# Logica_ADC.net
KiCad netlist of a schematic drawn in Altium Designer
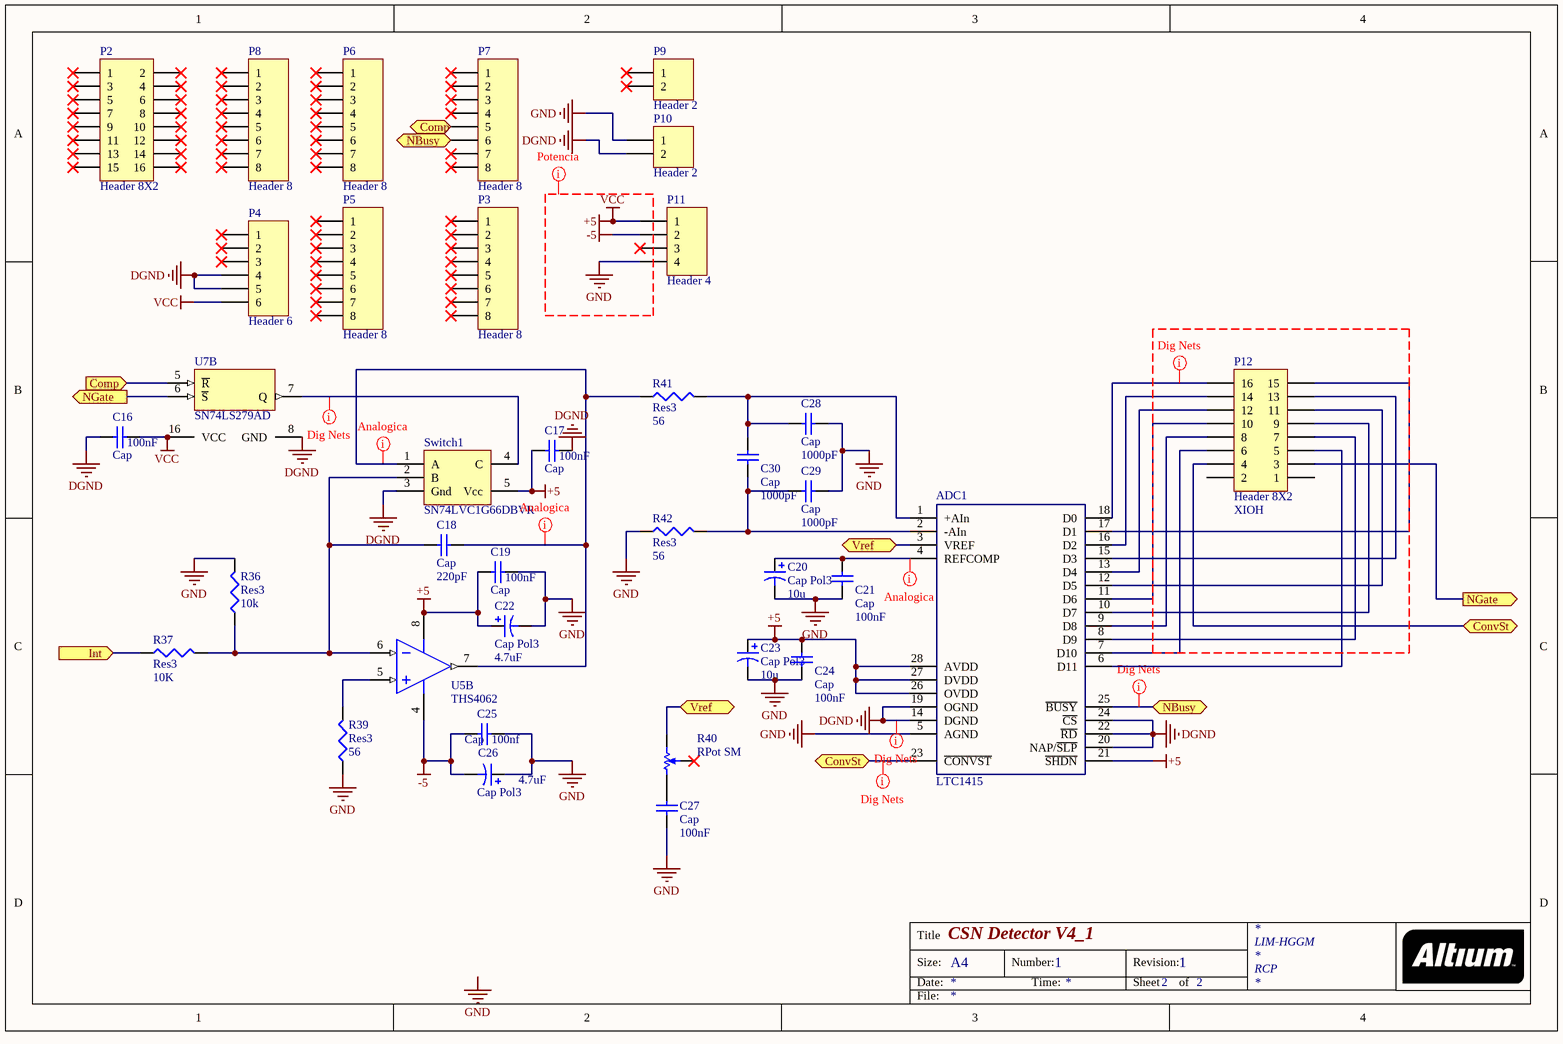
[diagram p0: Logica_ADC.SchDoc]

(export (version "E")
  (design (tool "Eeschema 10.0.6"))
  (components
    (comp (ref "ADC1")
      (value "LTC1415")
      (footprint "SO28_N")
      (libsource (lib "Integrated_Library1") (part "LTC1415"))
    )
    (comp (ref "C16")
      (value "Cap")
      (footprint "6-0805_N")
      (description "Capacitor")
      (fields (field (name "ALTIUM_VALUE") "100nF") (field (name "PUBLISHER") "Altium Limited"))
      (libsource (lib "Miscellaneous Devices") (part "Cap"))
    )
    (comp (ref "C17")
      (value "Cap")
      (footprint "6-0805_N")
      (description "Capacitor")
      (fields (field (name "ALTIUM_VALUE") "100nF") (field (name "PUBLISHER") "Altium Limited"))
      (libsource (lib "Miscellaneous Devices") (part "Cap"))
    )
    (comp (ref "C18")
      (value "Cap")
      (footprint "6-0805_N")
      (description "Capacitor")
      (fields (field (name "ALTIUM_VALUE") "220pF") (field (name "PUBLISHER") "Altium Limited"))
      (libsource (lib "Miscellaneous Devices") (part "Cap"))
    )
    (comp (ref "C19")
      (value "Cap")
      (footprint "6-0805_N")
      (description "Capacitor")
      (fields (field (name "ALTIUM_VALUE") "100nF") (field (name "PUBLISHER") "Altium Limited"))
      (libsource (lib "Miscellaneous Devices") (part "Cap"))
    )
    (comp (ref "C20")
      (value "Cap Pol3")
      (footprint "6-0805_N")
      (description "Polarized Capacitor (Surface Mount)")
      (fields (field (name "ALTIUM_VALUE") "10u") (field (name "PUBLISHER") "Altium Limited"))
      (libsource (lib "Miscellaneous Devices") (part "Cap Pol3"))
    )
    (comp (ref "C21")
      (value "Cap")
      (footprint "6-0805_N")
      (description "Capacitor")
      (fields (field (name "ALTIUM_VALUE") "100nF") (field (name "PUBLISHER") "Altium Limited"))
      (libsource (lib "Miscellaneous Devices") (part "Cap"))
    )
    (comp (ref "C22")
      (value "Cap Pol3")
      (footprint "6-0805_N")
      (description "Polarized Capacitor (Surface Mount)")
      (fields (field (name "ALTIUM_VALUE") "4.7uF") (field (name "PUBLISHER") "Altium Limited"))
      (libsource (lib "Miscellaneous Devices") (part "Cap Pol3"))
    )
    (comp (ref "C23")
      (value "Cap Pol3")
      (footprint "6-0805_N")
      (description "Polarized Capacitor (Surface Mount)")
      (fields (field (name "ALTIUM_VALUE") "10u") (field (name "PUBLISHER") "Altium Limited"))
      (libsource (lib "Miscellaneous Devices") (part "Cap Pol3"))
    )
    (comp (ref "C24")
      (value "Cap")
      (footprint "6-0805_N")
      (description "Capacitor")
      (fields (field (name "ALTIUM_VALUE") "100nF") (field (name "PUBLISHER") "Altium Limited"))
      (libsource (lib "Miscellaneous Devices") (part "Cap"))
    )
    (comp (ref "C25")
      (value "Cap")
      (footprint "6-0805_N")
      (description "Capacitor")
      (fields (field (name "ALTIUM_VALUE") "100nf") (field (name "PUBLISHER") "Altium Limited"))
      (libsource (lib "Miscellaneous Devices") (part "Cap"))
    )
    (comp (ref "C26")
      (value "Cap Pol3")
      (footprint "6-0805_N")
      (description "Polarized Capacitor (Surface Mount)")
      (fields (field (name "ALTIUM_VALUE") "4.7uF") (field (name "PUBLISHER") "Altium Limited"))
      (libsource (lib "Miscellaneous Devices") (part "Cap Pol3"))
    )
    (comp (ref "C27")
      (value "Cap")
      (footprint "6-0805_N")
      (description "Capacitor")
      (fields (field (name "ALTIUM_VALUE") "100nF") (field (name "PUBLISHER") "Altium Limited"))
      (libsource (lib "Miscellaneous Devices") (part "Cap"))
    )
    (comp (ref "C28")
      (value "Cap")
      (footprint "6-0805_N")
      (description "Capacitor")
      (fields (field (name "ALTIUM_VALUE") "1000pF") (field (name "PUBLISHER") "Altium Limited"))
      (libsource (lib "Miscellaneous Devices") (part "Cap"))
    )
    (comp (ref "C29")
      (value "Cap")
      (footprint "6-0805_N")
      (description "Capacitor")
      (fields (field (name "ALTIUM_VALUE") "1000pF") (field (name "PUBLISHER") "Altium Limited"))
      (libsource (lib "Miscellaneous Devices") (part "Cap"))
    )
    (comp (ref "C30")
      (value "Cap")
      (footprint "6-0805_N")
      (description "Capacitor")
      (fields (field (name "ALTIUM_VALUE") "1000pF") (field (name "PUBLISHER") "Altium Limited"))
      (libsource (lib "Miscellaneous Devices") (part "Cap"))
    )
    (comp (ref "P2")
      (value "Header 8X2")
      (footprint "HDR2X8")
      (description "Header, 8-Pin, Dual row")
      (fields (field (name "PUBLISHER") "Altium Limited"))
      (libsource (lib "") (part "Header 8X2_1"))
    )
    (comp (ref "P3")
      (value "Header 8")
      (footprint "HDR1X8")
      (description "Header, 8-Pin")
      (fields (field (name "PUBLISHER") "Altium Limited"))
      (libsource (lib "Miscellaneous Connectors") (part "Header 8"))
    )
    (comp (ref "P4")
      (value "Header 6")
      (footprint "HDR1X6")
      (description "Header, 6-Pin")
      (fields (field (name "PUBLISHER") "Altium Limited"))
      (libsource (lib "Miscellaneous Connectors") (part "Header 6"))
    )
    (comp (ref "P5")
      (value "Header 8")
      (footprint "HDR1X8")
      (description "Header, 8-Pin")
      (fields (field (name "PUBLISHER") "Altium Limited"))
      (libsource (lib "Miscellaneous Connectors") (part "Header 8"))
    )
    (comp (ref "P6")
      (value "Header 8")
      (footprint "HDR1X8")
      (description "Header, 8-Pin")
      (fields (field (name "PUBLISHER") "Altium Limited"))
      (libsource (lib "Miscellaneous Connectors") (part "Header 8"))
    )
    (comp (ref "P7")
      (value "Header 8")
      (footprint "HDR1X8")
      (description "Header, 8-Pin")
      (fields (field (name "PUBLISHER") "Altium Limited"))
      (libsource (lib "Miscellaneous Connectors") (part "Header 8"))
    )
    (comp (ref "P8")
      (value "Header 8")
      (footprint "HDR1X8")
      (description "Header, 8-Pin")
      (fields (field (name "PUBLISHER") "Altium Limited"))
      (libsource (lib "Miscellaneous Connectors") (part "Header 8"))
    )
    (comp (ref "P9")
      (value "Header 2")
      (footprint "HDR1X2")
      (description "Header, 2-Pin")
      (fields (field (name "PUBLISHER") "Altium Limited"))
      (libsource (lib "Miscellaneous Connectors") (part "Header 2"))
    )
    (comp (ref "P10")
      (value "Header 2")
      (footprint "HDR1X2")
      (description "Header, 2-Pin")
      (fields (field (name "PUBLISHER") "Altium Limited"))
      (libsource (lib "Miscellaneous Connectors") (part "Header 2"))
    )
    (comp (ref "P11")
      (value "Header 4")
      (footprint "HDR1X4")
      (description "Header, 4-Pin")
      (fields (field (name "PUBLISHER") "Altium Limited"))
      (libsource (lib "Miscellaneous Connectors") (part "Header 4"))
    )
    (comp (ref "P12")
      (value "Header 8X2")
      (footprint "HDR2X8")
      (description "Header, 8-Pin, Dual row")
      (fields (field (name "CON_ARDUINO") "XIOH") (field (name "PUBLISHER") "Altium Limited"))
      (libsource (lib "Miscellaneous Connectors") (part "Header 8X2"))
    )
    (comp (ref "R36")
      (value "Res3")
      (footprint "6-0805_N")
      (description "Resistor")
      (fields (field (name "ALTIUM_VALUE") "10k") (field (name "PUBLISHER") "Altium Limited"))
      (libsource (lib "Miscellaneous Devices") (part "Res3"))
    )
    (comp (ref "R37")
      (value "Res3")
      (footprint "6-0805_N")
      (description "Resistor")
      (fields (field (name "ALTIUM_VALUE") "10K") (field (name "PUBLISHER") "Altium Limited"))
      (libsource (lib "Miscellaneous Devices") (part "Res3"))
    )
    (comp (ref "R39")
      (value "Res3")
      (footprint "6-0805_N")
      (description "Resistor")
      (fields (field (name "ALTIUM_VALUE") "56") (field (name "PUBLISHER") "Altium Limited"))
      (libsource (lib "Miscellaneous Devices") (part "Res3"))
    )
    (comp (ref "R40")
      (value "RPot SM")
      (footprint "POT4MM-2")
      (description "Square Trimming Potentiometer")
      (fields (field (name "PUBLISHER") "Altium Limited"))
      (libsource (lib "Miscellaneous Devices") (part "RPot SM"))
    )
    (comp (ref "R41")
      (value "Res3")
      (footprint "6-0805_N")
      (description "Resistor")
      (fields (field (name "ALTIUM_VALUE") "56") (field (name "PUBLISHER") "Altium Limited"))
      (libsource (lib "Miscellaneous Devices") (part "Res3"))
    )
    (comp (ref "R42")
      (value "Res3")
      (footprint "6-0805_N")
      (description "Resistor")
      (fields (field (name "ALTIUM_VALUE") "56") (field (name "PUBLISHER") "Altium Limited"))
      (libsource (lib "Miscellaneous Devices") (part "Res3"))
    )
    (comp (ref "Switch1")
      (value "SN74LVC1G66DBVR")
      (footprint "SOT23-5_N")
      (libsource (lib "Integrated_Library1") (part "SN74LVC1G66DBVR"))
    )
    (comp (ref "U5")
      (value "THS4062")
      (footprint "S8_N")
      (description "Low Cost Dual Video Amplifier")
      (fields (field (name "PUBLISHER") "Altium Limited"))
      (libsource (lib "LT Video Amplifier") (part "LT1253CS8"))
    )
    (comp (ref "U7")
      (value "SN74LS279AD")
      (footprint "D016_N")
      (description "Quadruple S-R Latches")
      (fields (field (name "PUBLISHER") "Altium Limited"))
      (libsource (lib "TI Logic Latch") (part "SN74LS279AD"))
    )
  )
  (nets
    (net (code "1") (name "+5") (class "Default")
      (node (ref "ADC1") (pin "21") (pinfunction "~{SHDN}_21") (pintype "passive"))
      (node (ref "ADC1") (pin "26") (pinfunction "OVDD_26") (pintype "passive"))
      (node (ref "ADC1") (pin "27") (pinfunction "DVDD_27") (pintype "passive"))
      (node (ref "ADC1") (pin "28") (pinfunction "AVDD_28") (pintype "passive"))
      (node (ref "C16") (pin "1") (pinfunction "1_1") (pintype "passive"))
      (node (ref "C17") (pin "2") (pinfunction "2_2") (pintype "passive"))
      (node (ref "C19") (pin "2") (pinfunction "2_2") (pintype "passive"))
      (node (ref "C22") (pin "1") (pinfunction "1_1") (pintype "passive"))
      (node (ref "C23") (pin "1") (pinfunction "1_1") (pintype "passive"))
      (node (ref "C24") (pin "2") (pinfunction "2_2") (pintype "passive"))
      (node (ref "P11") (pin "1") (pinfunction "1_1") (pintype "passive"))
      (node (ref "P4") (pin "6") (pinfunction "6_6") (pintype "passive"))
      (node (ref "Switch1") (pin "5") (pinfunction "Vcc_5") (pintype "passive"))
      (node (ref "U5") (pin "8") (pinfunction "V+_8") (pintype "power_in"))
      (node (ref "U7") (pin "16") (pinfunction "VCC_16") (pintype "power_in"))
    )
    (net (code "2") (name "-5") (class "Default")
      (node (ref "C25") (pin "1") (pinfunction "1_1") (pintype "passive"))
      (node (ref "C26") (pin "2") (pinfunction "2_2") (pintype "passive"))
      (node (ref "P11") (pin "2") (pinfunction "2_2") (pintype "passive"))
      (node (ref "U5") (pin "4") (pinfunction "V-_4") (pintype "power_in"))
    )
    (net (code "3") (name "/Comp") (class "Default")
      (node (ref "P7") (pin "5") (pinfunction "5_5") (pintype "passive"))
      (node (ref "U7") (pin "5") (pinfunction "~{R}_5") (pintype "input"))
    )
    (net (code "4") (name "/ConvSt") (class "Default")
      (node (ref "ADC1") (pin "23") (pinfunction "~{CONVST}_23") (pintype "passive"))
      (node (ref "P12") (pin "4") (pinfunction "4_4") (pintype "passive"))
    )
    (net (code "5") (name "/Int") (class "Default")
      (node (ref "R37") (pin "1") (pinfunction "1_1") (pintype "passive"))
    )
    (net (code "6") (name "/NBusy") (class "Default")
      (node (ref "ADC1") (pin "25") (pinfunction "~{BUSY}_25") (pintype "passive"))
      (node (ref "P7") (pin "6") (pinfunction "6_6") (pintype "passive"))
    )
    (net (code "7") (name "/NGate") (class "Default")
      (node (ref "P12") (pin "3") (pinfunction "3_3") (pintype "passive"))
      (node (ref "U7") (pin "6") (pinfunction "~{S}_6") (pintype "input"))
    )
    (net (code "8") (name "/Vref") (class "Default")
      (node (ref "ADC1") (pin "3") (pinfunction "VREF_3") (pintype "passive"))
      (node (ref "R40") (pin "CW") (pinfunction "+_CW") (pintype "passive"))
    )
    (net (code "9") (name "DGND") (class "Default")
      (node (ref "ADC1") (pin "14") (pinfunction "DGND_14") (pintype "passive"))
      (node (ref "ADC1") (pin "19") (pinfunction "OGND_19") (pintype "passive"))
      (node (ref "ADC1") (pin "20") (pinfunction "NAP/~{SLP}_20") (pintype "passive"))
      (node (ref "ADC1") (pin "22") (pinfunction "~{RD}_22") (pintype "passive"))
      (node (ref "ADC1") (pin "24") (pinfunction "~{CS}_24") (pintype "passive"))
      (node (ref "ADC1") (pin "5") (pinfunction "AGND_5") (pintype "passive"))
      (node (ref "C16") (pin "2") (pinfunction "2_2") (pintype "passive"))
      (node (ref "C17") (pin "1") (pinfunction "1_1") (pintype "passive"))
      (node (ref "C19") (pin "1") (pinfunction "1_1") (pintype "passive"))
      (node (ref "C20") (pin "2") (pinfunction "2_2") (pintype "passive"))
      (node (ref "C21") (pin "1") (pinfunction "1_1") (pintype "passive"))
      (node (ref "C22") (pin "2") (pinfunction "2_2") (pintype "passive"))
      (node (ref "C23") (pin "2") (pinfunction "2_2") (pintype "passive"))
      (node (ref "C24") (pin "1") (pinfunction "1_1") (pintype "passive"))
      (node (ref "C25") (pin "2") (pinfunction "2_2") (pintype "passive"))
      (node (ref "C26") (pin "1") (pinfunction "1_1") (pintype "passive"))
      (node (ref "C27") (pin "2") (pinfunction "2_2") (pintype "passive"))
      (node (ref "C28") (pin "1") (pinfunction "1_1") (pintype "passive"))
      (node (ref "C29") (pin "1") (pinfunction "1_1") (pintype "passive"))
      (node (ref "P10") (pin "1") (pinfunction "1_1") (pintype "passive"))
      (node (ref "P10") (pin "2") (pinfunction "2_2") (pintype "passive"))
      (node (ref "P11") (pin "4") (pinfunction "4_4") (pintype "passive"))
      (node (ref "P4") (pin "4") (pinfunction "4_4") (pintype "passive"))
      (node (ref "P4") (pin "5") (pinfunction "5_5") (pintype "passive"))
      (node (ref "R36") (pin "2") (pinfunction "2_2") (pintype "passive"))
      (node (ref "R39") (pin "1") (pinfunction "1_1") (pintype "passive"))
      (node (ref "R42") (pin "1") (pinfunction "1_1") (pintype "passive"))
      (node (ref "Switch1") (pin "3") (pinfunction "Gnd_3") (pintype "passive"))
      (node (ref "U7") (pin "8") (pinfunction "GND_8") (pintype "power_in"))
    )
    (net (code "10") (name "Net-(ADC1-+AIn)") (class "Default")
      (node (ref "ADC1") (pin "1") (pinfunction "+AIn_1") (pintype "passive"))
      (node (ref "C28") (pin "2") (pinfunction "2_2") (pintype "passive"))
      (node (ref "C30") (pin "2") (pinfunction "2_2") (pintype "passive"))
      (node (ref "R41") (pin "2") (pinfunction "2_2") (pintype "passive"))
    )
    (net (code "11") (name "Net-(ADC1--AIn)") (class "Default")
      (node (ref "ADC1") (pin "2") (pinfunction "-AIn_2") (pintype "passive"))
      (node (ref "C29") (pin "2") (pinfunction "2_2") (pintype "passive"))
      (node (ref "C30") (pin "1") (pinfunction "1_1") (pintype "passive"))
      (node (ref "R42") (pin "2") (pinfunction "2_2") (pintype "passive"))
    )
    (net (code "12") (name "Net-(ADC1-D0)") (class "Default")
      (node (ref "ADC1") (pin "18") (pinfunction "D0_18") (pintype "passive"))
      (node (ref "P12") (pin "16") (pinfunction "16_16") (pintype "passive"))
    )
    (net (code "13") (name "Net-(ADC1-D1)") (class "Default")
      (node (ref "ADC1") (pin "17") (pinfunction "D1_17") (pintype "passive"))
      (node (ref "P12") (pin "15") (pinfunction "15_15") (pintype "passive"))
    )
    (net (code "14") (name "Net-(ADC1-D2)") (class "Default")
      (node (ref "ADC1") (pin "16") (pinfunction "D2_16") (pintype "passive"))
      (node (ref "P12") (pin "14") (pinfunction "14_14") (pintype "passive"))
    )
    (net (code "15") (name "Net-(ADC1-D3)") (class "Default")
      (node (ref "ADC1") (pin "15") (pinfunction "D3_15") (pintype "passive"))
      (node (ref "P12") (pin "13") (pinfunction "13_13") (pintype "passive"))
    )
    (net (code "16") (name "Net-(ADC1-D4)") (class "Default")
      (node (ref "ADC1") (pin "13") (pinfunction "D4_13") (pintype "passive"))
      (node (ref "P12") (pin "12") (pinfunction "12_12") (pintype "passive"))
    )
    (net (code "17") (name "Net-(ADC1-D5)") (class "Default")
      (node (ref "ADC1") (pin "12") (pinfunction "D5_12") (pintype "passive"))
      (node (ref "P12") (pin "11") (pinfunction "11_11") (pintype "passive"))
    )
    (net (code "18") (name "Net-(ADC1-D6)") (class "Default")
      (node (ref "ADC1") (pin "11") (pinfunction "D6_11") (pintype "passive"))
      (node (ref "P12") (pin "10") (pinfunction "10_10") (pintype "passive"))
    )
    (net (code "19") (name "Net-(ADC1-D7)") (class "Default")
      (node (ref "ADC1") (pin "10") (pinfunction "D7_10") (pintype "passive"))
      (node (ref "P12") (pin "9") (pinfunction "9_9") (pintype "passive"))
    )
    (net (code "20") (name "Net-(ADC1-D8)") (class "Default")
      (node (ref "ADC1") (pin "9") (pinfunction "D8_9") (pintype "passive"))
      (node (ref "P12") (pin "8") (pinfunction "8_8") (pintype "passive"))
    )
    (net (code "21") (name "Net-(ADC1-D9)") (class "Default")
      (node (ref "ADC1") (pin "8") (pinfunction "D9_8") (pintype "passive"))
      (node (ref "P12") (pin "7") (pinfunction "7_7") (pintype "passive"))
    )
    (net (code "22") (name "Net-(ADC1-D10)") (class "Default")
      (node (ref "ADC1") (pin "7") (pinfunction "D10_7") (pintype "passive"))
      (node (ref "P12") (pin "6") (pinfunction "6_6") (pintype "passive"))
    )
    (net (code "23") (name "Net-(ADC1-D11)") (class "Default")
      (node (ref "ADC1") (pin "6") (pinfunction "D11_6") (pintype "passive"))
      (node (ref "P12") (pin "5") (pinfunction "5_5") (pintype "passive"))
    )
    (net (code "24") (name "Net-(ADC1-REFCOMP)") (class "Default")
      (node (ref "ADC1") (pin "4") (pinfunction "REFCOMP_4") (pintype "passive"))
      (node (ref "C20") (pin "1") (pinfunction "1_1") (pintype "passive"))
      (node (ref "C21") (pin "2") (pinfunction "2_2") (pintype "passive"))
    )
    (net (code "25") (name "Net-(R40--)") (class "Default")
      (node (ref "C27") (pin "1") (pinfunction "1_1") (pintype "passive"))
      (node (ref "R40") (pin "CCW") (pinfunction "-_CCW") (pintype "passive"))
    )
    (net (code "26") (name "Net-(Switch1-A)") (class "Default")
      (node (ref "C18") (pin "2") (pinfunction "2_2") (pintype "passive"))
      (node (ref "R41") (pin "1") (pinfunction "1_1") (pintype "passive"))
      (node (ref "Switch1") (pin "1") (pinfunction "A_1") (pintype "passive"))
      (node (ref "U5") (pin "7") (pinfunction "OUT_7") (pintype "output"))
    )
    (net (code "27") (name "Net-(Switch1-B)") (class "Default")
      (node (ref "C18") (pin "1") (pinfunction "1_1") (pintype "passive"))
      (node (ref "R36") (pin "1") (pinfunction "1_1") (pintype "passive"))
      (node (ref "R37") (pin "2") (pinfunction "2_2") (pintype "passive"))
      (node (ref "Switch1") (pin "2") (pinfunction "B_2") (pintype "passive"))
      (node (ref "U5") (pin "6") (pinfunction "IN-_6") (pintype "input"))
    )
    (net (code "28") (name "Net-(Switch1-C)") (class "Default")
      (node (ref "Switch1") (pin "4") (pinfunction "C_4") (pintype "passive"))
      (node (ref "U7") (pin "7") (pinfunction "Q_7") (pintype "output"))
    )
    (net (code "29") (name "Net-(U5B-IN+)") (class "Default")
      (node (ref "R39") (pin "2") (pinfunction "2_2") (pintype "passive"))
      (node (ref "U5") (pin "5") (pinfunction "IN+_5") (pintype "input"))
    )
    (net (code "30") (name "unconnected-(P2-Pad1)") (class "Default")
      (node (ref "P2") (pin "1") (pinfunction "1_1") (pintype "passive+no_connect"))
    )
    (net (code "31") (name "unconnected-(P2-Pad2)") (class "Default")
      (node (ref "P2") (pin "2") (pinfunction "2_2") (pintype "passive+no_connect"))
    )
    (net (code "32") (name "unconnected-(P2-Pad3)") (class "Default")
      (node (ref "P2") (pin "3") (pinfunction "3_3") (pintype "passive+no_connect"))
    )
    (net (code "33") (name "unconnected-(P2-Pad4)") (class "Default")
      (node (ref "P2") (pin "4") (pinfunction "4_4") (pintype "passive+no_connect"))
    )
    (net (code "34") (name "unconnected-(P2-Pad5)") (class "Default")
      (node (ref "P2") (pin "5") (pinfunction "5_5") (pintype "passive+no_connect"))
    )
    (net (code "35") (name "unconnected-(P2-Pad6)") (class "Default")
      (node (ref "P2") (pin "6") (pinfunction "6_6") (pintype "passive+no_connect"))
    )
    (net (code "36") (name "unconnected-(P2-Pad7)") (class "Default")
      (node (ref "P2") (pin "7") (pinfunction "7_7") (pintype "passive+no_connect"))
    )
    (net (code "37") (name "unconnected-(P2-Pad8)") (class "Default")
      (node (ref "P2") (pin "8") (pinfunction "8_8") (pintype "passive+no_connect"))
    )
    (net (code "38") (name "unconnected-(P2-Pad9)") (class "Default")
      (node (ref "P2") (pin "9") (pinfunction "9_9") (pintype "passive+no_connect"))
    )
    (net (code "39") (name "unconnected-(P2-Pad10)") (class "Default")
      (node (ref "P2") (pin "10") (pinfunction "10_10") (pintype "passive+no_connect"))
    )
    (net (code "40") (name "unconnected-(P2-Pad11)") (class "Default")
      (node (ref "P2") (pin "11") (pinfunction "11_11") (pintype "passive+no_connect"))
    )
    (net (code "41") (name "unconnected-(P2-Pad12)") (class "Default")
      (node (ref "P2") (pin "12") (pinfunction "12_12") (pintype "passive+no_connect"))
    )
    (net (code "42") (name "unconnected-(P2-Pad13)") (class "Default")
      (node (ref "P2") (pin "13") (pinfunction "13_13") (pintype "passive+no_connect"))
    )
    (net (code "43") (name "unconnected-(P2-Pad14)") (class "Default")
      (node (ref "P2") (pin "14") (pinfunction "14_14") (pintype "passive+no_connect"))
    )
    (net (code "44") (name "unconnected-(P2-Pad15)") (class "Default")
      (node (ref "P2") (pin "15") (pinfunction "15_15") (pintype "passive+no_connect"))
    )
    (net (code "45") (name "unconnected-(P2-Pad16)") (class "Default")
      (node (ref "P2") (pin "16") (pinfunction "16_16") (pintype "passive+no_connect"))
    )
    (net (code "46") (name "unconnected-(P3-Pad1)") (class "Default")
      (node (ref "P3") (pin "1") (pinfunction "1_1") (pintype "passive+no_connect"))
    )
    (net (code "47") (name "unconnected-(P3-Pad2)") (class "Default")
      (node (ref "P3") (pin "2") (pinfunction "2_2") (pintype "passive+no_connect"))
    )
    (net (code "48") (name "unconnected-(P3-Pad3)") (class "Default")
      (node (ref "P3") (pin "3") (pinfunction "3_3") (pintype "passive+no_connect"))
    )
    (net (code "49") (name "unconnected-(P3-Pad4)") (class "Default")
      (node (ref "P3") (pin "4") (pinfunction "4_4") (pintype "passive+no_connect"))
    )
    (net (code "50") (name "unconnected-(P3-Pad5)") (class "Default")
      (node (ref "P3") (pin "5") (pinfunction "5_5") (pintype "passive+no_connect"))
    )
    (net (code "51") (name "unconnected-(P3-Pad6)") (class "Default")
      (node (ref "P3") (pin "6") (pinfunction "6_6") (pintype "passive+no_connect"))
    )
    (net (code "52") (name "unconnected-(P3-Pad7)") (class "Default")
      (node (ref "P3") (pin "7") (pinfunction "7_7") (pintype "passive+no_connect"))
    )
    (net (code "53") (name "unconnected-(P3-Pad8)") (class "Default")
      (node (ref "P3") (pin "8") (pinfunction "8_8") (pintype "passive+no_connect"))
    )
    (net (code "54") (name "unconnected-(P4-Pad1)") (class "Default")
      (node (ref "P4") (pin "1") (pinfunction "1_1") (pintype "passive+no_connect"))
    )
    (net (code "55") (name "unconnected-(P4-Pad2)") (class "Default")
      (node (ref "P4") (pin "2") (pinfunction "2_2") (pintype "passive+no_connect"))
    )
    (net (code "56") (name "unconnected-(P4-Pad3)") (class "Default")
      (node (ref "P4") (pin "3") (pinfunction "3_3") (pintype "passive+no_connect"))
    )
    (net (code "57") (name "unconnected-(P5-Pad1)") (class "Default")
      (node (ref "P5") (pin "1") (pinfunction "1_1") (pintype "passive+no_connect"))
    )
    (net (code "58") (name "unconnected-(P5-Pad2)") (class "Default")
      (node (ref "P5") (pin "2") (pinfunction "2_2") (pintype "passive+no_connect"))
    )
    (net (code "59") (name "unconnected-(P5-Pad3)") (class "Default")
      (node (ref "P5") (pin "3") (pinfunction "3_3") (pintype "passive+no_connect"))
    )
    (net (code "60") (name "unconnected-(P5-Pad4)") (class "Default")
      (node (ref "P5") (pin "4") (pinfunction "4_4") (pintype "passive+no_connect"))
    )
    (net (code "61") (name "unconnected-(P5-Pad5)") (class "Default")
      (node (ref "P5") (pin "5") (pinfunction "5_5") (pintype "passive+no_connect"))
    )
    (net (code "62") (name "unconnected-(P5-Pad6)") (class "Default")
      (node (ref "P5") (pin "6") (pinfunction "6_6") (pintype "passive+no_connect"))
    )
    (net (code "63") (name "unconnected-(P5-Pad7)") (class "Default")
      (node (ref "P5") (pin "7") (pinfunction "7_7") (pintype "passive+no_connect"))
    )
    (net (code "64") (name "unconnected-(P5-Pad8)") (class "Default")
      (node (ref "P5") (pin "8") (pinfunction "8_8") (pintype "passive+no_connect"))
    )
    (net (code "65") (name "unconnected-(P6-Pad1)") (class "Default")
      (node (ref "P6") (pin "1") (pinfunction "1_1") (pintype "passive+no_connect"))
    )
    (net (code "66") (name "unconnected-(P6-Pad2)") (class "Default")
      (node (ref "P6") (pin "2") (pinfunction "2_2") (pintype "passive+no_connect"))
    )
    (net (code "67") (name "unconnected-(P6-Pad3)") (class "Default")
      (node (ref "P6") (pin "3") (pinfunction "3_3") (pintype "passive+no_connect"))
    )
    (net (code "68") (name "unconnected-(P6-Pad4)") (class "Default")
      (node (ref "P6") (pin "4") (pinfunction "4_4") (pintype "passive+no_connect"))
    )
    (net (code "69") (name "unconnected-(P6-Pad5)") (class "Default")
      (node (ref "P6") (pin "5") (pinfunction "5_5") (pintype "passive+no_connect"))
    )
    (net (code "70") (name "unconnected-(P6-Pad6)") (class "Default")
      (node (ref "P6") (pin "6") (pinfunction "6_6") (pintype "passive+no_connect"))
    )
    (net (code "71") (name "unconnected-(P6-Pad7)") (class "Default")
      (node (ref "P6") (pin "7") (pinfunction "7_7") (pintype "passive+no_connect"))
    )
    (net (code "72") (name "unconnected-(P6-Pad8)") (class "Default")
      (node (ref "P6") (pin "8") (pinfunction "8_8") (pintype "passive+no_connect"))
    )
    (net (code "73") (name "unconnected-(P7-Pad1)") (class "Default")
      (node (ref "P7") (pin "1") (pinfunction "1_1") (pintype "passive+no_connect"))
    )
    (net (code "74") (name "unconnected-(P7-Pad2)") (class "Default")
      (node (ref "P7") (pin "2") (pinfunction "2_2") (pintype "passive+no_connect"))
    )
    (net (code "75") (name "unconnected-(P7-Pad3)") (class "Default")
      (node (ref "P7") (pin "3") (pinfunction "3_3") (pintype "passive+no_connect"))
    )
    (net (code "76") (name "unconnected-(P7-Pad4)") (class "Default")
      (node (ref "P7") (pin "4") (pinfunction "4_4") (pintype "passive+no_connect"))
    )
    (net (code "77") (name "unconnected-(P7-Pad7)") (class "Default")
      (node (ref "P7") (pin "7") (pinfunction "7_7") (pintype "passive+no_connect"))
    )
    (net (code "78") (name "unconnected-(P7-Pad8)") (class "Default")
      (node (ref "P7") (pin "8") (pinfunction "8_8") (pintype "passive+no_connect"))
    )
    (net (code "79") (name "unconnected-(P8-Pad1)") (class "Default")
      (node (ref "P8") (pin "1") (pinfunction "1_1") (pintype "passive+no_connect"))
    )
    (net (code "80") (name "unconnected-(P8-Pad2)") (class "Default")
      (node (ref "P8") (pin "2") (pinfunction "2_2") (pintype "passive+no_connect"))
    )
    (net (code "81") (name "unconnected-(P8-Pad3)") (class "Default")
      (node (ref "P8") (pin "3") (pinfunction "3_3") (pintype "passive+no_connect"))
    )
    (net (code "82") (name "unconnected-(P8-Pad4)") (class "Default")
      (node (ref "P8") (pin "4") (pinfunction "4_4") (pintype "passive+no_connect"))
    )
    (net (code "83") (name "unconnected-(P8-Pad5)") (class "Default")
      (node (ref "P8") (pin "5") (pinfunction "5_5") (pintype "passive+no_connect"))
    )
    (net (code "84") (name "unconnected-(P8-Pad6)") (class "Default")
      (node (ref "P8") (pin "6") (pinfunction "6_6") (pintype "passive+no_connect"))
    )
    (net (code "85") (name "unconnected-(P8-Pad7)") (class "Default")
      (node (ref "P8") (pin "7") (pinfunction "7_7") (pintype "passive+no_connect"))
    )
    (net (code "86") (name "unconnected-(P8-Pad8)") (class "Default")
      (node (ref "P8") (pin "8") (pinfunction "8_8") (pintype "passive+no_connect"))
    )
    (net (code "87") (name "unconnected-(P9-Pad1)") (class "Default")
      (node (ref "P9") (pin "1") (pinfunction "1_1") (pintype "passive+no_connect"))
    )
    (net (code "88") (name "unconnected-(P9-Pad2)") (class "Default")
      (node (ref "P9") (pin "2") (pinfunction "2_2") (pintype "passive+no_connect"))
    )
    (net (code "89") (name "unconnected-(P11-Pad3)") (class "Default")
      (node (ref "P11") (pin "3") (pinfunction "3_3") (pintype "passive+no_connect"))
    )
    (net (code "90") (name "unconnected-(P12-Pad1)") (class "Default")
      (node (ref "P12") (pin "1") (pinfunction "1_1") (pintype "passive"))
    )
    (net (code "91") (name "unconnected-(P12-Pad2)") (class "Default")
      (node (ref "P12") (pin "2") (pinfunction "2_2") (pintype "passive"))
    )
    (net (code "92") (name "unconnected-(R40-PadW)") (class "Default")
      (node (ref "R40") (pin "W") (pinfunction "W_W") (pintype "passive+no_connect"))
    )
  )
)
